# BatteryCharge.net
KiCad netlist of a schematic drawn in Altium Designer
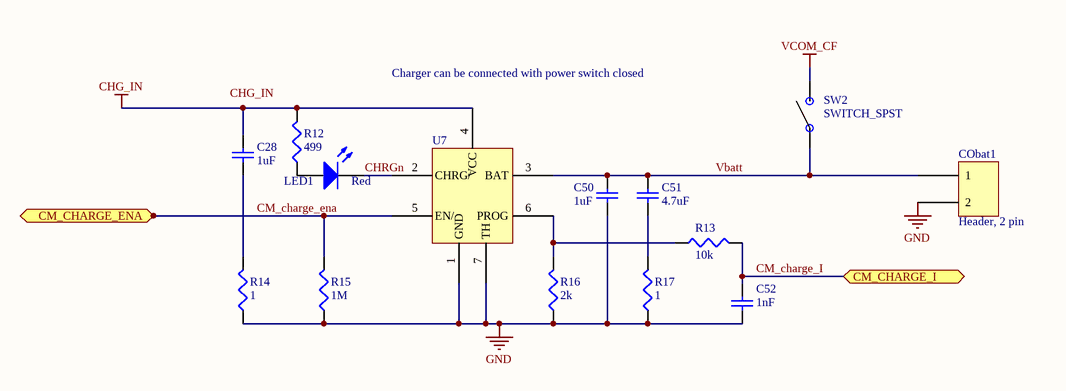
[diagram p0: BatteryCharge.SchDoc]

(export (version "E")
  (design (tool "Eeschema 10.0.6"))
  (components
    (comp (ref "C28")
      (value "1uF")
      (footprint "0402")
      (description "CAP CER 1UF 16V X5R 0402")
      (fields (field (name "MANUFACTURER") "TDK") (field (name "Comment") "C1005X5R1C105M050BC"))
      (libsource (lib "Custom") (part "Cap"))
    )
    (comp (ref "C50")
      (value "1uF")
      (footprint "0402")
      (description "CAP CER 1UF 16V X5R 0402")
      (fields (field (name "MANUFACTURER") "TDK") (field (name "Comment") "C1005X5R1C105M050BC"))
      (libsource (lib "Custom") (part "Cap"))
    )
    (comp (ref "C51")
      (value "4.7uF")
      (footprint "0402")
      (description "CAP CER 4.7UF 35V X5R 0603")
      (fields (field (name "MANUFACTURER") "Murata") (field (name "Comment") "GRM188R6YA475KE15D"))
      (libsource (lib "Custom") (part "Cap"))
    )
    (comp (ref "C52")
      (value "1nF")
      (footprint "0402")
      (description "CAP CER 1000PF 50V X5R 0402")
      (fields (field (name "MANUFACTURER") "Murata") (field (name "Comment") "GRM155R61H102KA01D"))
      (libsource (lib "Custom") (part "Cap"))
    )
    (comp (ref "CObat1")
      (value "Header, 2 pin")
      (footprint "Pin Header, 1x2, TH")
      (description "Header 1x2")
      (fields (field (name "MANUFACTURER") "Samtec"))
      (libsource (lib "CM") (part "Header, 2 pin"))
    )
    (comp (ref "LED1")
      (value "~")
      (footprint "0603")
      (description "LED RED CLEAR 0603 SMD")
      (fields (field (name "MANUFACTURER") "Rohm") (field (name "COLOR") "Red"))
      (libsource (lib "Custom") (part "LED"))
    )
    (comp (ref "R12")
      (value "499")
      (footprint "0402")
      (description "RES SMD 499 OHM 1% 1/10W 0402")
      (fields (field (name "MANUFACTURER") "Panasonic") (field (name "POWER") "1/10W"))
      (libsource (lib "Custom") (part "Resistor"))
    )
    (comp (ref "R13")
      (value "10k")
      (footprint "0402")
      (description "RES SMD 10K OHM 1% 1/10W 0402")
      (fields (field (name "MANUFACTURER") "Panasonic") (field (name "POWER") "1/10W"))
      (libsource (lib "Custom") (part "Resistor"))
    )
    (comp (ref "R14")
      (value "1")
      (footprint "0402")
      (description "RES SMD 1 OHM 1% 1/6W 0402")
      (fields (field (name "MANUFACTURER") "Panasonic") (field (name "POWER") "1/6W"))
      (libsource (lib "Custom") (part "Resistor"))
    )
    (comp (ref "R15")
      (value "1M")
      (footprint "0402")
      (description "RES SMD 1M OHM 1% 1/10W 0402")
      (fields (field (name "MANUFACTURER") "Panasonic") (field (name "POWER") "1/10W"))
      (libsource (lib "Custom") (part "Resistor"))
    )
    (comp (ref "R16")
      (value "2k")
      (footprint "0402")
      (description "RES SMD 2K OHM 1% 1/10W 0402")
      (fields (field (name "MANUFACTURER") "Panasonic") (field (name "POWER") "1/10W"))
      (libsource (lib "Custom") (part "Resistor"))
    )
    (comp (ref "R17")
      (value "1")
      (footprint "0402")
      (description "RES SMD 1 OHM 1% 1/6W 0402")
      (fields (field (name "MANUFACTURER") "Panasonic") (field (name "POWER") "1/6W"))
      (libsource (lib "Custom") (part "Resistor"))
    )
    (comp (ref "SW2")
      (value "SWITCH_SPST")
      (footprint "SWITCH_SPST_CHS-01TB")
      (description "SWITCH SLIDE DIP SPST 100MA 6V")
      (fields (field (name "MANUFACTURER") "Copal"))
      (libsource (lib "CM") (part "SWITCH_SPST"))
    )
    (comp (ref "U7")
      (value "LTC4065EDC#TRMPBF")
      (footprint "DFN-6_LT")
      (description "IC CHARGER BATT LI-ON 6-DFN")
      (fields (field (name "MANUFACTURER") "LT"))
      (libsource (lib "Custom") (part "LTC4065EDC"))
    )
  )
  (nets
    (net (code "1") (name "/CHRGn") (class "Default")
      (node (ref "LED1") (pin "2") (pinfunction "K_2") (pintype "passive"))
      (node (ref "U7") (pin "2") (pinfunction "CHRG/_2") (pintype "passive"))
    )
    (net (code "2") (name "/CM_charge_I") (class "Default")
      (node (ref "C52") (pin "2") (pinfunction "2_2") (pintype "passive"))
      (node (ref "R13") (pin "2") (pinfunction "2_2") (pintype "passive"))
    )
    (net (code "3") (name "/CM_charge_ena") (class "Default")
      (node (ref "R15") (pin "2") (pinfunction "2_2") (pintype "passive"))
      (node (ref "U7") (pin "5") (pinfunction "EN/_5") (pintype "passive"))
    )
    (net (code "4") (name "/Vbatt") (class "Default")
      (node (ref "C50") (pin "2") (pinfunction "2_2") (pintype "passive"))
      (node (ref "C51") (pin "2") (pinfunction "2_2") (pintype "passive"))
      (node (ref "CObat1") (pin "1") (pinfunction "1_1") (pintype "passive"))
      (node (ref "SW2") (pin "2") (pinfunction "2_2") (pintype "passive"))
      (node (ref "U7") (pin "3") (pinfunction "BAT_3") (pintype "passive"))
    )
    (net (code "5") (name "CHG_IN") (class "Default")
      (node (ref "C28") (pin "2") (pinfunction "2_2") (pintype "passive"))
      (node (ref "R12") (pin "2") (pinfunction "2_2") (pintype "passive"))
      (node (ref "U7") (pin "4") (pinfunction "VCC_4") (pintype "passive"))
    )
    (net (code "6") (name "GND") (class "Default")
      (node (ref "C50") (pin "1") (pinfunction "1_1") (pintype "passive"))
      (node (ref "C52") (pin "1") (pinfunction "1_1") (pintype "passive"))
      (node (ref "CObat1") (pin "2") (pinfunction "2_2") (pintype "passive"))
      (node (ref "R14") (pin "1") (pinfunction "1_1") (pintype "passive"))
      (node (ref "R15") (pin "1") (pinfunction "1_1") (pintype "passive"))
      (node (ref "R16") (pin "1") (pinfunction "1_1") (pintype "passive"))
      (node (ref "R17") (pin "1") (pinfunction "1_1") (pintype "passive"))
      (node (ref "U7") (pin "1") (pinfunction "GND_1") (pintype "passive"))
      (node (ref "U7") (pin "7") (pinfunction "TH_7") (pintype "passive"))
    )
    (net (code "7") (name "Net-(C28-Pad1)") (class "Default")
      (node (ref "C28") (pin "1") (pinfunction "1_1") (pintype "passive"))
      (node (ref "R14") (pin "2") (pinfunction "2_2") (pintype "passive"))
    )
    (net (code "8") (name "Net-(C51-Pad1)") (class "Default")
      (node (ref "C51") (pin "1") (pinfunction "1_1") (pintype "passive"))
      (node (ref "R17") (pin "2") (pinfunction "2_2") (pintype "passive"))
    )
    (net (code "9") (name "Net-(LED1-A)") (class "Default")
      (node (ref "LED1") (pin "1") (pinfunction "A_1") (pintype "passive"))
      (node (ref "R12") (pin "1") (pinfunction "1_1") (pintype "passive"))
    )
    (net (code "10") (name "Net-(U7-PROG)") (class "Default")
      (node (ref "R13") (pin "1") (pinfunction "1_1") (pintype "passive"))
      (node (ref "R16") (pin "2") (pinfunction "2_2") (pintype "passive"))
      (node (ref "U7") (pin "6") (pinfunction "PROG_6") (pintype "passive"))
    )
    (net (code "11") (name "VCOM_CF") (class "Default")
      (node (ref "SW2") (pin "1") (pinfunction "1_1") (pintype "passive"))
    )
  )
)
